# STEPPER_MOTOR.net
KiCad netlist of a schematic drawn in Altium Designer
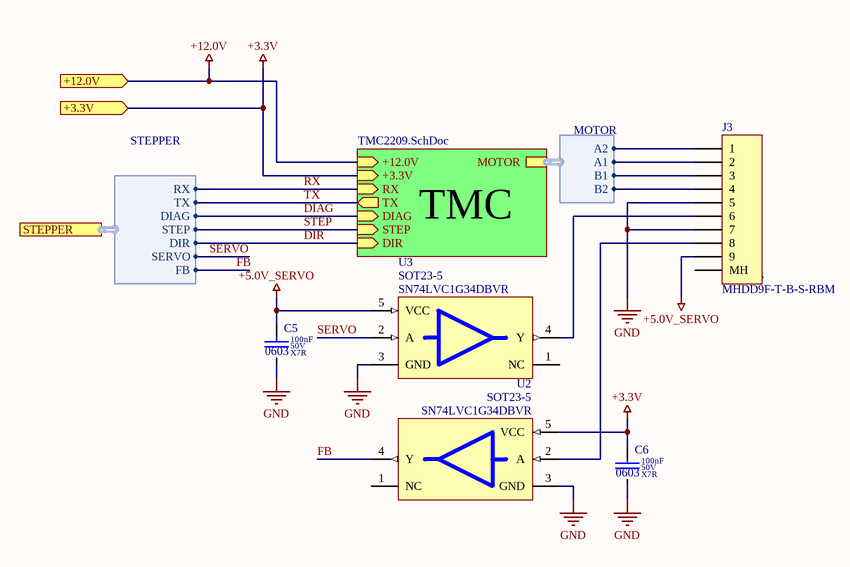
[diagram p0: STEPPER_MOTOR.SchDoc]

(export (version "E")
  (design (tool "Eeschema 10.0.6"))
  (components
    (comp (ref "C5")
      (value "100nF")
      (footprint "C_0603_1608")
      (description "Capacitor")
      (fields
        (field (name "DIELECTRIC") "X7R")
        (field (name "VOLTAGE") "50V")
        (field (name "SCH_FOOTPRINT") "0603")
        (field (name "PART NUMBER") "C_100nF_50V_X7R_0603_5")
        (field (name "MANUFACTURER") "Samsung")
      )
      (libsource (lib "Library") (part "C"))
    )
    (comp (ref "C6")
      (value "100nF")
      (footprint "C_0603_1608")
      (description "Capacitor")
      (fields
        (field (name "DIELECTRIC") "X7R")
        (field (name "VOLTAGE") "50V")
        (field (name "SCH_FOOTPRINT") "0603")
        (field (name "PART NUMBER") "C_100nF_50V_X7R_0603_5")
        (field (name "MANUFACTURER") "Samsung")
      )
      (libsource (lib "Library") (part "C"))
    )
    (comp (ref "J3")
      (value "MHDD9F-T-B-S-RBM")
      (footprint "J_DSUB_MHDD9F-T-B-S-RBM")
      (description "Header, 9-Pin")
      (fields
        (field (name "SCH_FOOTPRINT") "J_DSUB")
        (field (name "PART NUMBER") "J_DSUB")
        (field (name "MANUFACTURER") "MH Connectors")
      )
      (libsource (lib "Library") (part "J_DSUB"))
    )
    (comp (ref "U2")
      (value "SN74LVC1G34DBVR")
      (footprint "SOT23-5_SC74A_SOT753_M")
      (fields
        (field (name "SCH_FOOTPRINT") "SOT23-5")
        (field (name "PART NUMBER") "U_SN74LVC1G34DBVR")
        (field (name "MANUFACTURER") "Texas Instruments")
        (field (name "Comment") "Single Buffer Gate")
      )
      (libsource (lib "Library") (part "U_SN74LVC1G34_DBV_DCK_DRL"))
    )
    (comp (ref "U3")
      (value "SN74LVC1G34DBVR")
      (footprint "SOT23-5_SC74A_SOT753_M")
      (fields
        (field (name "SCH_FOOTPRINT") "SOT23-5")
        (field (name "PART NUMBER") "U_SN74LVC1G34DBVR")
        (field (name "MANUFACTURER") "Texas Instruments")
        (field (name "Comment") "Single Buffer Gate")
      )
      (libsource (lib "") (part "U_SN74LVC1G34_DBV_DCK_DRL_1"))
    )
  )
  (nets
    (net (code "3") (name "+3.3V") (class "Default")
      (node (ref "C6") (pin "1") (pinfunction "1_1") (pintype "passive"))
      (node (ref "U2") (pin "5") (pinfunction "VCC_5") (pintype "input"))
    )
    (net (code "4") (name "+5.0V_SERVO") (class "Default")
      (node (ref "C5") (pin "1") (pinfunction "1_1") (pintype "passive"))
      (node (ref "J3") (pin "9") (pinfunction "9_9") (pintype "passive"))
      (node (ref "U3") (pin "5") (pinfunction "VCC_5") (pintype "input"))
    )
    (net (code "6") (name "/A1") (class "Default")
      (node (ref "J3") (pin "2") (pinfunction "2_2") (pintype "passive"))
    )
    (net (code "7") (name "/A2") (class "Default")
      (node (ref "J3") (pin "1") (pinfunction "1_1") (pintype "passive"))
    )
    (net (code "8") (name "/B1") (class "Default")
      (node (ref "J3") (pin "3") (pinfunction "3_3") (pintype "passive"))
    )
    (net (code "9") (name "/B2") (class "Default")
      (node (ref "J3") (pin "4") (pinfunction "4_4") (pintype "passive"))
    )
    (net (code "12") (name "/FB") (class "Default")
      (node (ref "U2") (pin "4") (pinfunction "Y_4") (pintype "output"))
    )
    (net (code "14") (name "/SERVO") (class "Default")
      (node (ref "U3") (pin "2") (pinfunction "A_2") (pintype "input"))
    )
    (net (code "19") (name "GND") (class "Default")
      (node (ref "C5") (pin "2") (pinfunction "2_2") (pintype "passive"))
      (node (ref "C6") (pin "2") (pinfunction "2_2") (pintype "passive"))
      (node (ref "J3") (pin "5") (pinfunction "5_5") (pintype "passive"))
      (node (ref "J3") (pin "7") (pinfunction "7_7") (pintype "passive"))
      (node (ref "U2") (pin "3") (pinfunction "GND_3") (pintype "power_in"))
      (node (ref "U3") (pin "3") (pinfunction "GND_3") (pintype "power_in"))
    )
    (net (code "20") (name "Net-(U2-A)") (class "Default")
      (node (ref "J3") (pin "8") (pinfunction "8_8") (pintype "passive"))
      (node (ref "U2") (pin "2") (pinfunction "A_2") (pintype "input"))
    )
    (net (code "21") (name "Net-(U3-Y)") (class "Default")
      (node (ref "J3") (pin "6") (pinfunction "6_6") (pintype "passive"))
      (node (ref "U3") (pin "4") (pinfunction "Y_4") (pintype "output"))
    )
    (net (code "22") (name "unconnected-(J3-PadMH)") (class "Default")
      (node (ref "J3") (pin "MH") (pinfunction "MH_MH") (pintype "passive"))
    )
    (net (code "23") (name "unconnected-(U2-NC-Pad1)") (class "Default")
      (node (ref "U2") (pin "1") (pinfunction "NC_1") (pintype "passive"))
    )
    (net (code "24") (name "unconnected-(U3-NC-Pad1)") (class "Default")
      (node (ref "U3") (pin "1") (pinfunction "NC_1") (pintype "passive"))
    )
  )
)
